# EVB1.net
KiCad netlist of a schematic drawn in Altium Designer
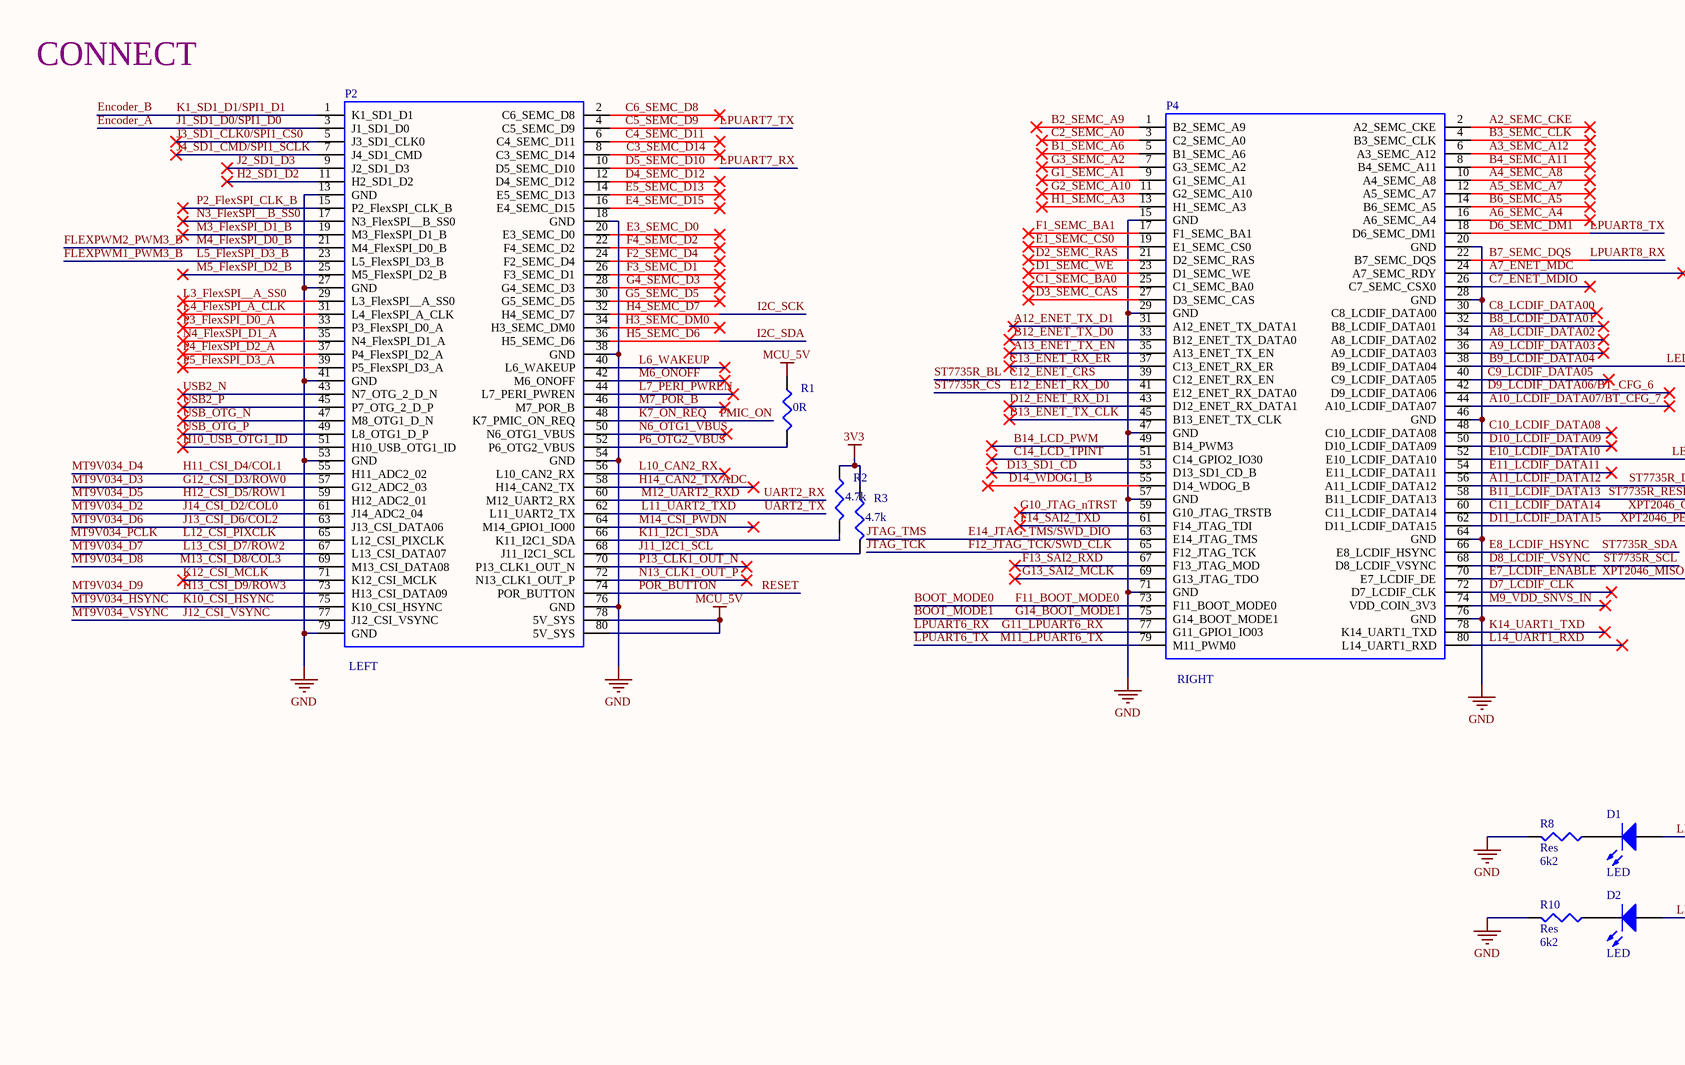
[diagram p0: EVB1.SchDoc, left]
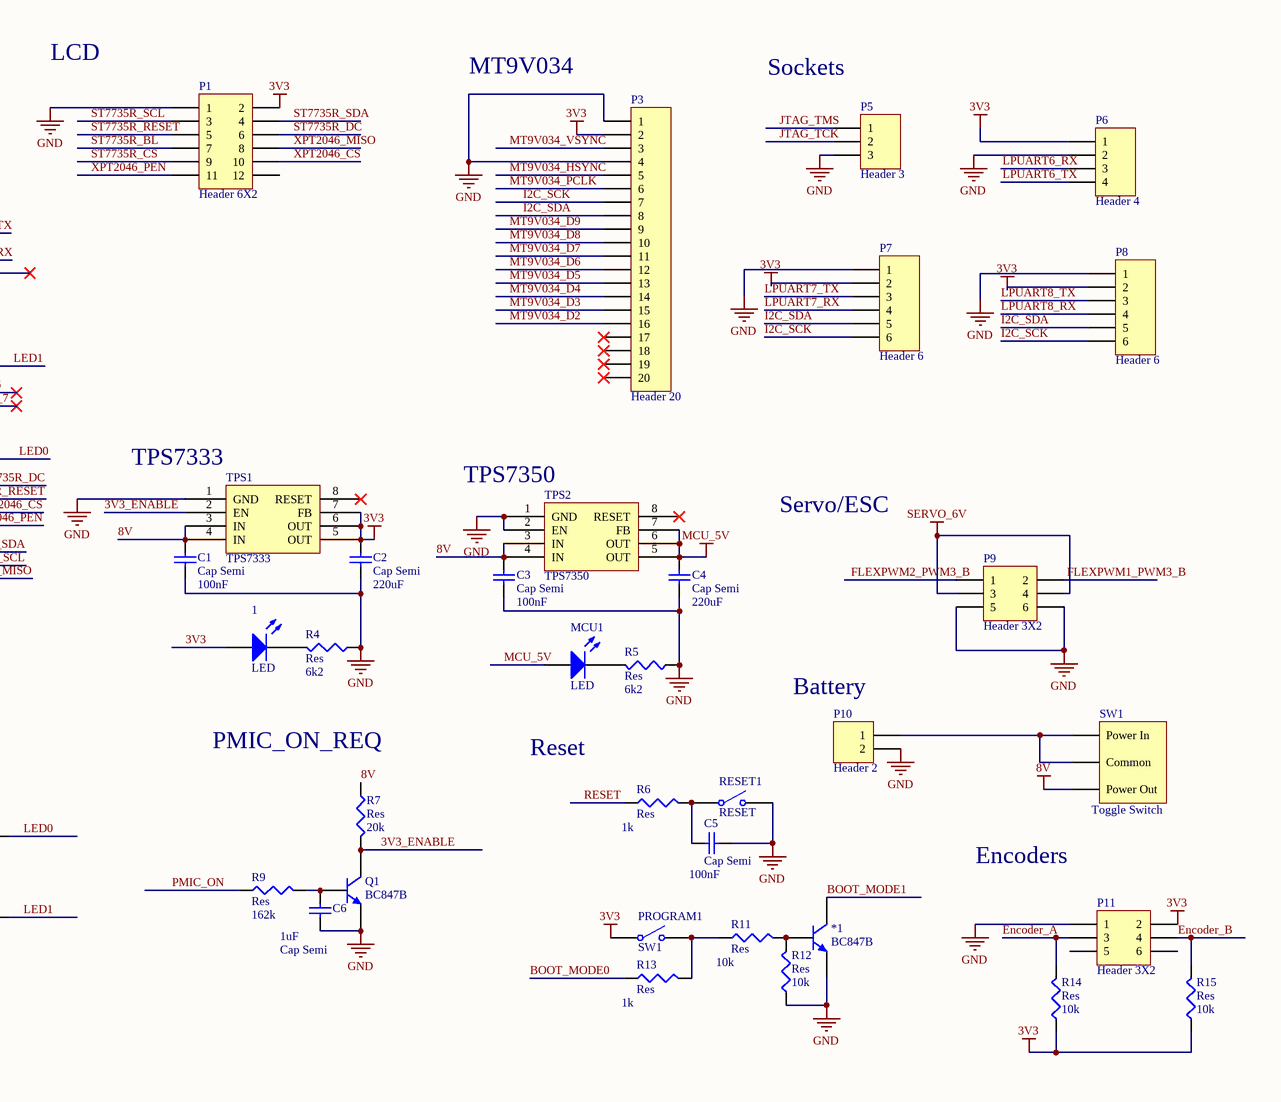
[diagram p1: EVB1.SchDoc, right]

(export (version "E")
  (design (tool "Eeschema 10.0.6"))
  (components
    (comp (ref "*1")
      (value "BC847B")
      (footprint "SOT-23")
      (description "NPN")
      (libsource (lib "SmartCar2018") (part "BC847B"))
    )
    (comp (ref "1")
      (value "LED")
      (footprint "LED 0805")
      (description "Typical GaAs LED")
      (fields (field (name "PUBLISHER") "Altium Limited"))
      (libsource (lib "SmartCar2018") (part "LED"))
    )
    (comp (ref "C1")
      (value "Cap Semi")
      (footprint "CC2012-0805")
      (description "Capacitor (Semiconductor SIM Model)")
      (fields (field (name "ALTIUM_VALUE") "100nF") (field (name "PUBLISHER") "Altium Limited"))
      (libsource (lib "SmartCar2018") (part "Cap Semi"))
    )
    (comp (ref "C2")
      (value "Cap Semi")
      (footprint "CC3216-1206")
      (description "Capacitor (Semiconductor SIM Model)")
      (fields (field (name "ALTIUM_VALUE") "220uF") (field (name "PUBLISHER") "Altium Limited"))
      (libsource (lib "SmartCar2018") (part "Cap Semi"))
    )
    (comp (ref "C3")
      (value "Cap Semi")
      (footprint "CC2012-0805")
      (description "Capacitor (Semiconductor SIM Model)")
      (fields (field (name "ALTIUM_VALUE") "100nF") (field (name "PUBLISHER") "Altium Limited"))
      (libsource (lib "SmartCar2018") (part "Cap Semi"))
    )
    (comp (ref "C4")
      (value "Cap Semi")
      (footprint "CC3216-1206")
      (description "Capacitor (Semiconductor SIM Model)")
      (fields (field (name "ALTIUM_VALUE") "220uF") (field (name "PUBLISHER") "Altium Limited"))
      (libsource (lib "SmartCar2018") (part "Cap Semi"))
    )
    (comp (ref "C5")
      (value "Cap Semi")
      (footprint "CC2012-0805")
      (description "Capacitor (Semiconductor SIM Model)")
      (fields (field (name "ALTIUM_VALUE") "100nF") (field (name "PUBLISHER") "Altium Limited"))
      (libsource (lib "SmartCar2018") (part "Cap Semi"))
    )
    (comp (ref "C6")
      (value "Cap Semi")
      (footprint "CC2012-0805")
      (description "Capacitor (Semiconductor SIM Model)")
      (fields (field (name "ALTIUM_VALUE") "1uF") (field (name "PUBLISHER") "Altium Limited"))
      (libsource (lib "SmartCar2018") (part "Cap Semi"))
    )
    (comp (ref "D1")
      (value "LED")
      (footprint "LED 0805")
      (description "Typical GaAs LED")
      (fields (field (name "PUBLISHER") "Altium Limited"))
      (libsource (lib "SmartCar2018") (part "LED"))
    )
    (comp (ref "D2")
      (value "LED")
      (footprint "LED 0805")
      (description "Typical GaAs LED")
      (fields (field (name "PUBLISHER") "Altium Limited"))
      (libsource (lib "SmartCar2018") (part "LED"))
    )
    (comp (ref "MCU1")
      (value "LED")
      (footprint "LED 0805")
      (description "Typical GaAs LED")
      (fields (field (name "PUBLISHER") "Altium Limited"))
      (libsource (lib "SmartCar2018") (part "LED"))
    )
    (comp (ref "P1")
      (value "Header 6X2")
      (footprint "HDR2X6")
      (description "Header, 6-Pin, Dual row")
      (fields (field (name "PUBLISHER") "Altium Limited"))
      (libsource (lib "SmartCar2018") (part "Header 6X2"))
    )
    (comp (ref "P2")
      (value "LEFT")
      (footprint "CON80:CON80")
      (description "Header, 30-Pin, Dual row")
      (fields (field (name "PUBLISHER") "Altium Limited"))
      (libsource (lib "PCB_RT1052_1") (part "Header40X2_left"))
    )
    (comp (ref "P3")
      (value "Header 20")
      (footprint "FPC0.5_20P")
      (description "Header, 20-Pin")
      (fields (field (name "PUBLISHER") "Altium Limited"))
      (libsource (lib "SmartCar2018") (part "Header 20"))
    )
    (comp (ref "P4")
      (value "RIGHT")
      (footprint "CON80:CON80")
      (description "Header, 30-Pin, Dual row")
      (fields (field (name "PUBLISHER") "Altium Limited"))
      (libsource (lib "PCB_RT1052_1") (part "Header40X2_right"))
    )
    (comp (ref "P5")
      (value "Header 3")
      (footprint "HDR1X3")
      (description "Header, 3-Pin")
      (fields (field (name "PUBLISHER") "Altium Limited"))
      (libsource (lib "SmartCar2018") (part "Header 3"))
    )
    (comp (ref "P6")
      (value "Header 4")
      (footprint "HDR1X4")
      (description "Header, 4-Pin")
      (fields (field (name "PUBLISHER") "Altium Limited"))
      (libsource (lib "SmartCar2018") (part "Header 4"))
    )
    (comp (ref "P7")
      (value "Header 6")
      (footprint "HDR1X6")
      (description "Header, 6-Pin")
      (fields (field (name "PUBLISHER") "Altium Limited"))
      (libsource (lib "SmartCar2018") (part "Header 6"))
    )
    (comp (ref "P8")
      (value "Header 6")
      (footprint "HDR1X6")
      (description "Header, 6-Pin")
      (fields (field (name "PUBLISHER") "Altium Limited"))
      (libsource (lib "SmartCar2018") (part "Header 6"))
    )
    (comp (ref "P9")
      (value "Header 3X2")
      (footprint "HDR2X3")
      (description "Header, 3-Pin, Dual row")
      (fields (field (name "PUBLISHER") "Altium Limited"))
      (libsource (lib "SmartCar2018") (part "Header 3X2"))
    )
    (comp (ref "P10")
      (value "Header 2")
      (footprint "XT30PW-M")
      (description "Header, 2-Pin")
      (fields (field (name "PUBLISHER") "Altium Limited"))
      (libsource (lib "SmartCar2018") (part "Header 2"))
    )
    (comp (ref "P11")
      (value "Header 3X2")
      (footprint "SMMD HEADER 2X3")
      (description "Header, 3-Pin, Dual row")
      (fields (field (name "PUBLISHER") "Altium Limited"))
      (libsource (lib "SmartCar2018") (part "Header 3X2"))
    )
    (comp (ref "PROGRAM1")
      (value "SW1")
      (footprint "PUSHBUTTOM")
      (description "Single-Pole, Single-Throw Switch")
      (fields (field (name "PUBLISHER") "Altium Limited"))
      (libsource (lib "SmartCar2018") (part "SW-SPST"))
    )
    (comp (ref "Q1")
      (value "BC847B")
      (footprint "SOT-23")
      (description "NPN")
      (libsource (lib "SmartCar2018") (part "BC847B"))
    )
    (comp (ref "R1")
      (value "0R")
      (footprint "CR2012-0805")
      (description "Resistor")
      (fields (field (name "PUBLISHER") "Altium Limited"))
      (libsource (lib "SmartCar2018") (part "Res"))
    )
    (comp (ref "R2")
      (value "4.7k")
      (footprint "CR2012-0805")
      (description "Resistor")
      (fields (field (name "PUBLISHER") "Altium Limited"))
      (libsource (lib "SmartCar2018") (part "Res"))
    )
    (comp (ref "R3")
      (value "4.7k")
      (footprint "CR2012-0805")
      (description "Resistor")
      (fields (field (name "PUBLISHER") "Altium Limited"))
      (libsource (lib "SmartCar2018") (part "Res"))
    )
    (comp (ref "R4")
      (value "Res")
      (footprint "CR2012-0805")
      (description "Resistor")
      (fields (field (name "ALTIUM_VALUE") "6k2") (field (name "PUBLISHER") "Altium Limited"))
      (libsource (lib "SmartCar2018") (part "Res"))
    )
    (comp (ref "R5")
      (value "Res")
      (footprint "CR2012-0805")
      (description "Resistor")
      (fields (field (name "ALTIUM_VALUE") "6k2") (field (name "PUBLISHER") "Altium Limited"))
      (libsource (lib "SmartCar2018") (part "Res"))
    )
    (comp (ref "R6")
      (value "Res")
      (footprint "CR2012-0805")
      (description "Resistor")
      (fields (field (name "ALTIUM_VALUE") "1k") (field (name "PUBLISHER") "Altium Limited"))
      (libsource (lib "SmartCar2018") (part "Res"))
    )
    (comp (ref "R7")
      (value "Res")
      (footprint "CR2012-0805")
      (description "Resistor")
      (fields (field (name "ALTIUM_VALUE") "20k") (field (name "PUBLISHER") "Altium Limited"))
      (libsource (lib "SmartCar2018") (part "Res"))
    )
    (comp (ref "R8")
      (value "Res")
      (footprint "CR2012-0805")
      (description "Resistor")
      (fields (field (name "ALTIUM_VALUE") "6k2") (field (name "PUBLISHER") "Altium Limited"))
      (libsource (lib "SmartCar2018") (part "Res"))
    )
    (comp (ref "R9")
      (value "Res")
      (footprint "CR2012-0805")
      (description "Resistor")
      (fields (field (name "ALTIUM_VALUE") "162k") (field (name "PUBLISHER") "Altium Limited"))
      (libsource (lib "SmartCar2018") (part "Res"))
    )
    (comp (ref "R10")
      (value "Res")
      (footprint "CR2012-0805")
      (description "Resistor")
      (fields (field (name "ALTIUM_VALUE") "6k2") (field (name "PUBLISHER") "Altium Limited"))
      (libsource (lib "SmartCar2018") (part "Res"))
    )
    (comp (ref "R11")
      (value "Res")
      (footprint "CR2012-0805")
      (description "Resistor")
      (fields (field (name "ALTIUM_VALUE") "10k") (field (name "PUBLISHER") "Altium Limited"))
      (libsource (lib "SmartCar2018") (part "Res"))
    )
    (comp (ref "R12")
      (value "Res")
      (footprint "CR2012-0805")
      (description "Resistor")
      (fields (field (name "ALTIUM_VALUE") "10k") (field (name "PUBLISHER") "Altium Limited"))
      (libsource (lib "SmartCar2018") (part "Res"))
    )
    (comp (ref "R13")
      (value "Res")
      (footprint "CR2012-0805")
      (description "Resistor")
      (fields (field (name "ALTIUM_VALUE") "1k") (field (name "PUBLISHER") "Altium Limited"))
      (libsource (lib "SmartCar2018") (part "Res"))
    )
    (comp (ref "R14")
      (value "Res")
      (footprint "CR2012-0805")
      (description "Resistor")
      (fields (field (name "ALTIUM_VALUE") "10k") (field (name "PUBLISHER") "Altium Limited"))
      (libsource (lib "SmartCar2018") (part "Res"))
    )
    (comp (ref "R15")
      (value "Res")
      (footprint "CR2012-0805")
      (description "Resistor")
      (fields (field (name "ALTIUM_VALUE") "10k") (field (name "PUBLISHER") "Altium Limited"))
      (libsource (lib "SmartCar2018") (part "Res"))
    )
    (comp (ref "RESET1")
      (value "RESET")
      (footprint "PUSHBUTTOM")
      (description "Single-Pole, Single-Throw Switch")
      (fields (field (name "PUBLISHER") "Altium Limited"))
      (libsource (lib "SmartCar2018") (part "SW-SPST"))
    )
    (comp (ref "SW1")
      (value "Toggle Switch")
      (footprint "ToggleSwitch")
      (description "Power toggle switch")
      (libsource (lib "SmartCar2018") (part "ToggleSwitch"))
    )
    (comp (ref "TPS1")
      (value "TPS7333")
      (footprint "TPS7333")
      (libsource (lib "SmartCar2018") (part "TPS7333"))
    )
    (comp (ref "TPS2")
      (value "TPS7350")
      (footprint "TPS7333")
      (libsource (lib "SmartCar2018") (part "TPS7333"))
    )
  )
  (nets
    (net (code "1") (name "/3V3_ENABLE") (class "Default")
      (node (ref "Q1") (pin "3") (pinfunction "C_3") (pintype "passive"))
      (node (ref "R7") (pin "2") (pinfunction "2_2") (pintype "passive"))
      (node (ref "TPS1") (pin "2") (pinfunction "EN_2") (pintype "passive"))
    )
    (net (code "2") (name "/A2_SEMC_CKE") (class "Default")
      (node (ref "P4") (pin "2") (pinfunction "A2_SEMC_CKE_2") (pintype "passive+no_connect"))
    )
    (net (code "3") (name "/A3_SEMC_A12") (class "Default")
      (node (ref "P4") (pin "6") (pinfunction "A3_SEMC_A12_6") (pintype "passive+no_connect"))
    )
    (net (code "4") (name "/A4_SEMC_A8") (class "Default")
      (node (ref "P4") (pin "10") (pinfunction "A4_SEMC_A8_10") (pintype "passive+no_connect"))
    )
    (net (code "5") (name "/A5_SEMC_A7") (class "Default")
      (node (ref "P4") (pin "12") (pinfunction "A5_SEMC_A7_12") (pintype "passive+no_connect"))
    )
    (net (code "6") (name "/A6_SEMC_A4") (class "Default")
      (node (ref "P4") (pin "16") (pinfunction "A6_SEMC_A4_16") (pintype "passive+no_connect"))
    )
    (net (code "7") (name "/A7_ENET_MDC") (class "Default")
      (node (ref "P4") (pin "24") (pinfunction "A7_SEMC_RDY_24") (pintype "passive+no_connect"))
    )
    (net (code "8") (name "/A8_LCDIF_DATA02") (class "Default")
      (node (ref "P4") (pin "34") (pinfunction "A8_LCDIF_DATA02_34") (pintype "passive+no_connect"))
    )
    (net (code "9") (name "/A9_LCDIF_DATA03") (class "Default")
      (node (ref "P4") (pin "36") (pinfunction "A9_LCDIF_DATA03_36") (pintype "passive+no_connect"))
    )
    (net (code "10") (name "/A10_LCDIF_DATA07{slash}BT_CFG_7") (class "Default")
      (node (ref "P4") (pin "44") (pinfunction "A10_LCDIF_DATA07_44") (pintype "passive+no_connect"))
    )
    (net (code "11") (name "/A11_LCDIF_DATA12") (class "Default")
      (node (ref "P1") (pin "6") (pinfunction "6_6") (pintype "passive"))
      (node (ref "P4") (pin "56") (pinfunction "A11_LCDIF_DATA12_56") (pintype "passive"))
    )
    (net (code "13") (name "/A12_ENET_TX_D1") (class "Default")
      (node (ref "P4") (pin "31") (pinfunction "A12_ENET_TX_DATA1_31") (pintype "passive"))
    )
    (net (code "14") (name "/A13_ENET_TX_EN") (class "Default")
      (node (ref "P4") (pin "35") (pinfunction "A13_ENET_TX_EN_35") (pintype "passive+no_connect"))
    )
    (net (code "15") (name "/B1_SEMC_A6") (class "Default")
      (node (ref "P4") (pin "5") (pinfunction "B1_SEMC_A6_5") (pintype "passive+no_connect"))
    )
    (net (code "16") (name "/B2_SEMC_A9") (class "Default")
      (node (ref "P4") (pin "1") (pinfunction "B2_SEMC_A9_1") (pintype "passive+no_connect"))
    )
    (net (code "17") (name "/B3_SEMC_CLK") (class "Default")
      (node (ref "P4") (pin "4") (pinfunction "B3_SEMC_CLK_4") (pintype "passive+no_connect"))
    )
    (net (code "18") (name "/B4_SEMC_A11") (class "Default")
      (node (ref "P4") (pin "8") (pinfunction "B4_SEMC_A11_8") (pintype "passive+no_connect"))
    )
    (net (code "19") (name "/B6_SEMC_A5") (class "Default")
      (node (ref "P4") (pin "14") (pinfunction "B6_SEMC_A5_14") (pintype "passive+no_connect"))
    )
    (net (code "20") (name "/B7_SEMC_DQS") (class "Default")
      (node (ref "P4") (pin "22") (pinfunction "B7_SEMC_DQS_22") (pintype "passive"))
      (node (ref "P8") (pin "4") (pinfunction "4_4") (pintype "passive"))
    )
    (net (code "21") (name "/B8_LCDIF_DATA01") (class "Default")
      (node (ref "P4") (pin "32") (pinfunction "B8_LCDIF_DATA01_32") (pintype "passive+no_connect"))
    )
    (net (code "22") (name "/B9_LCDIF_DATA04") (class "Default")
      (node (ref "D2") (pin "1") (pinfunction "A_1") (pintype "passive"))
      (node (ref "P4") (pin "38") (pinfunction "B9_LCDIF_DATA04_38") (pintype "passive"))
    )
    (net (code "23") (name "/B11_LCDIF_DATA13") (class "Default")
      (node (ref "P1") (pin "5") (pinfunction "5_5") (pintype "passive"))
      (node (ref "P4") (pin "58") (pinfunction "B11_LCDIF_DATA13_58") (pintype "passive"))
    )
    (net (code "24") (name "/B12_ENET_TX_D0") (class "Default")
      (node (ref "P4") (pin "33") (pinfunction "B12_ENET_TX_DATA0_33") (pintype "passive+no_connect"))
    )
    (net (code "25") (name "/B13_ENET_TX_CLK") (class "Default")
      (node (ref "P4") (pin "45") (pinfunction "B13_ENET_TX_CLK_45") (pintype "passive+no_connect"))
    )
    (net (code "26") (name "/B14_LCD_PWM") (class "Default")
      (node (ref "P4") (pin "49") (pinfunction "B14_PWM3_49") (pintype "passive+no_connect"))
    )
    (net (code "27") (name "/BOOT_MODE0") (class "Default")
      (node (ref "P4") (pin "73") (pinfunction "F11_BOOT_MODE0_73") (pintype "passive"))
      (node (ref "R13") (pin "1") (pinfunction "1_1") (pintype "passive"))
    )
    (net (code "28") (name "/BOOT_MODE1") (class "Default")
      (node (ref "*1") (pin "3") (pinfunction "C_3") (pintype "passive"))
      (node (ref "P4") (pin "75") (pinfunction "G14_BOOT_MODE1_75") (pintype "passive"))
    )
    (net (code "29") (name "/C1_SEMC_BA0") (class "Default")
      (node (ref "P4") (pin "25") (pinfunction "C1_SEMC_BA0_25") (pintype "passive+no_connect"))
    )
    (net (code "30") (name "/C2_SEMC_A0") (class "Default")
      (node (ref "P4") (pin "3") (pinfunction "C2_SEMC_A0_3") (pintype "passive+no_connect"))
    )
    (net (code "31") (name "/C3_SEMC_D14") (class "Default")
      (node (ref "P2") (pin "8") (pinfunction "C3_SEMC_D14_8") (pintype "passive+no_connect"))
    )
    (net (code "32") (name "/C4_SEMC_D11") (class "Default")
      (node (ref "P2") (pin "6") (pinfunction "C4_SEMC_D11_6") (pintype "passive+no_connect"))
    )
    (net (code "33") (name "/C5_SEMC_D9") (class "Default")
      (node (ref "P2") (pin "4") (pinfunction "C5_SEMC_D9_4") (pintype "passive"))
      (node (ref "P7") (pin "3") (pinfunction "3_3") (pintype "passive"))
    )
    (net (code "34") (name "/C6_SEMC_D8") (class "Default")
      (node (ref "P2") (pin "2") (pinfunction "C6_SEMC_D8_2") (pintype "passive+no_connect"))
    )
    (net (code "35") (name "/C7_ENET_MDIO") (class "Default")
      (node (ref "P4") (pin "26") (pinfunction "C7_SEMC_CSX0_26") (pintype "passive+no_connect"))
    )
    (net (code "36") (name "/C8_LCDIF_DATA00") (class "Default")
      (node (ref "P4") (pin "30") (pinfunction "C8_LCDIF_DATA00_30") (pintype "passive+no_connect"))
    )
    (net (code "37") (name "/C9_LCDIF_DATA05") (class "Default")
      (node (ref "P4") (pin "40") (pinfunction "C9_LCDIF_DATA05_40") (pintype "passive+no_connect"))
    )
    (net (code "38") (name "/C10_LCDIF_DATA08") (class "Default")
      (node (ref "P4") (pin "48") (pinfunction "C10_LCDIF_DATA08_48") (pintype "passive+no_connect"))
    )
    (net (code "39") (name "/C11_LCDIF_DATA14") (class "Default")
      (node (ref "P1") (pin "10") (pinfunction "10_10") (pintype "passive"))
      (node (ref "P4") (pin "60") (pinfunction "C11_LCDIF_DATA14_60") (pintype "passive"))
    )
    (net (code "40") (name "/C12_ENET_CRS") (class "Default")
      (node (ref "P1") (pin "7") (pinfunction "7_7") (pintype "passive"))
      (node (ref "P4") (pin "39") (pinfunction "C12_ENET_RX_EN_39") (pintype "passive"))
    )
    (net (code "41") (name "/C13_ENET_RX_ER") (class "Default")
      (node (ref "P4") (pin "37") (pinfunction "C13_ENET_RX_ER_37") (pintype "passive+no_connect"))
    )
    (net (code "42") (name "/C14_LCD_TPINT") (class "Default")
      (node (ref "P4") (pin "51") (pinfunction "C14_GPIO2_IO30_51") (pintype "passive+no_connect"))
    )
    (net (code "43") (name "/D1_SEMC_WE") (class "Default")
      (node (ref "P4") (pin "23") (pinfunction "D1_SEMC_WE_23") (pintype "passive+no_connect"))
    )
    (net (code "44") (name "/D2_SEMC_RAS") (class "Default")
      (node (ref "P4") (pin "21") (pinfunction "D2_SEMC_RAS_21") (pintype "passive+no_connect"))
    )
    (net (code "45") (name "/D3_SEMC_CAS") (class "Default")
      (node (ref "P4") (pin "27") (pinfunction "D3_SEMC_CAS_27") (pintype "passive+no_connect"))
    )
    (net (code "46") (name "/D4_SEMC_D12") (class "Default")
      (node (ref "P2") (pin "12") (pinfunction "D4_SEMC_D12_12") (pintype "passive+no_connect"))
    )
    (net (code "47") (name "/D5_SEMC_D10") (class "Default")
      (node (ref "P2") (pin "10") (pinfunction "D5_SEMC_D10_10") (pintype "passive"))
      (node (ref "P7") (pin "4") (pinfunction "4_4") (pintype "passive"))
    )
    (net (code "48") (name "/D6_SEMC_DM1") (class "Default")
      (node (ref "P4") (pin "18") (pinfunction "D6_SEMC_DM1_18") (pintype "passive"))
      (node (ref "P8") (pin "3") (pinfunction "3_3") (pintype "passive"))
    )
    (net (code "49") (name "/D7_LCDIF_CLK") (class "Default")
      (node (ref "P4") (pin "72") (pinfunction "D7_LCDIF_CLK_72") (pintype "passive+no_connect"))
    )
    (net (code "50") (name "/D8_LCDIF_VSYNC") (class "Default")
      (node (ref "P1") (pin "3") (pinfunction "3_3") (pintype "passive"))
      (node (ref "P4") (pin "68") (pinfunction "D8_LCDIF_VSYNC_68") (pintype "passive"))
    )
    (net (code "51") (name "/D9_LCDIF_DATA06{slash}BT_CFG_6") (class "Default")
      (node (ref "P4") (pin "42") (pinfunction "D9_LCDIF_DATA06_42") (pintype "passive+no_connect"))
    )
    (net (code "52") (name "/D10_LCDIF_DATA09") (class "Default")
      (node (ref "P4") (pin "50") (pinfunction "D10_LCDIF_DATA09_50") (pintype "passive+no_connect"))
    )
    (net (code "53") (name "/D11_LCDIF_DATA15") (class "Default")
      (node (ref "P1") (pin "11") (pinfunction "11_11") (pintype "passive"))
      (node (ref "P4") (pin "62") (pinfunction "D11_LCDIF_DATA15_62") (pintype "passive"))
    )
    (net (code "54") (name "/D12_ENET_RX_D1") (class "Default")
      (node (ref "P4") (pin "43") (pinfunction "D12_ENET_RX_DATA1_43") (pintype "passive+no_connect"))
    )
    (net (code "55") (name "/D13_SD1_CD") (class "Default")
      (node (ref "P4") (pin "53") (pinfunction "D13_SD1_CD_B_53") (pintype "passive+no_connect"))
    )
    (net (code "56") (name "/D14_WDOG1_B") (class "Default")
      (node (ref "P4") (pin "55") (pinfunction "D14_WDOG_B_55") (pintype "passive+no_connect"))
    )
    (net (code "57") (name "/E1_SEMC_CS0") (class "Default")
      (node (ref "P4") (pin "19") (pinfunction "E1_SEMC_CS0_19") (pintype "passive+no_connect"))
    )
    (net (code "58") (name "/E3_SEMC_D0") (class "Default")
      (node (ref "P2") (pin "20") (pinfunction "E3_SEMC_D0_20") (pintype "passive+no_connect"))
    )
    (net (code "59") (name "/E4_SEMC_D15") (class "Default")
      (node (ref "P2") (pin "16") (pinfunction "E4_SEMC_D15_16") (pintype "passive+no_connect"))
    )
    (net (code "60") (name "/E5_SEMC_D13") (class "Default")
      (node (ref "P2") (pin "14") (pinfunction "E5_SEMC_D13_14") (pintype "passive+no_connect"))
    )
    (net (code "61") (name "/E7_LCDIF_ENABLE") (class "Default")
      (node (ref "P1") (pin "8") (pinfunction "8_8") (pintype "passive"))
      (node (ref "P4") (pin "70") (pinfunction "E7_LCDIF_DE_70") (pintype "passive"))
    )
    (net (code "62") (name "/E8_LCDIF_HSYNC") (class "Default")
      (node (ref "P1") (pin "4") (pinfunction "4_4") (pintype "passive"))
      (node (ref "P4") (pin "66") (pinfunction "E8_LCDIF_HSYNC_66") (pintype "passive"))
    )
    (net (code "63") (name "/E10_LCDIF_DATA10") (class "Default")
      (node (ref "D1") (pin "1") (pinfunction "A_1") (pintype "passive"))
      (node (ref "P4") (pin "52") (pinfunction "E10_LCDIF_DATA10_52") (pintype "passive"))
    )
    (net (code "64") (name "/E11_LCDIF_DATA11") (class "Default")
      (node (ref "P4") (pin "54") (pinfunction "E11_LCDIF_DATA11_54") (pintype "passive+no_connect"))
    )
    (net (code "65") (name "/E12_ENET_RX_D0") (class "Default")
      (node (ref "P1") (pin "9") (pinfunction "9_9") (pintype "passive"))
      (node (ref "P4") (pin "41") (pinfunction "E12_ENET_RX_DATA0_41") (pintype "passive"))
    )
    (net (code "66") (name "/E14_JTAG_TMS{slash}SWD_DIO") (class "Default")
      (node (ref "P4") (pin "63") (pinfunction "E14_JTAG_TMS_63") (pintype "passive"))
      (node (ref "P5") (pin "1") (pinfunction "1_1") (pintype "passive"))
    )
    (net (code "67") (name "/Encoder_A") (class "Default")
      (node (ref "P11") (pin "3") (pinfunction "3_3") (pintype "passive"))
      (node (ref "P2") (pin "3") (pinfunction "J1_SD1_D0_3") (pintype "passive"))
      (node (ref "R14") (pin "2") (pinfunction "2_2") (pintype "passive"))
    )
    (net (code "68") (name "/Encoder_B") (class "Default")
      (node (ref "P11") (pin "4") (pinfunction "4_4") (pintype "passive"))
      (node (ref "P2") (pin "1") (pinfunction "K1_SD1_D1_1") (pintype "passive"))
      (node (ref "R15") (pin "2") (pinfunction "2_2") (pintype "passive"))
    )
    (net (code "69") (name "/F1_SEMC_BA1") (class "Default")
      (node (ref "P4") (pin "17") (pinfunction "F1_SEMC_BA1_17") (pintype "passive+no_connect"))
    )
    (net (code "70") (name "/F2_SEMC_D4") (class "Default")
      (node (ref "P2") (pin "24") (pinfunction "F2_SEMC_D4_24") (pintype "passive+no_connect"))
    )
    (net (code "71") (name "/F3_SEMC_D1") (class "Default")
      (node (ref "P2") (pin "26") (pinfunction "F3_SEMC_D1_26") (pintype "passive+no_connect"))
    )
    (net (code "72") (name "/F4_SEMC_D2") (class "Default")
      (node (ref "P2") (pin "22") (pinfunction "F4_SEMC_D2_22") (pintype "passive+no_connect"))
    )
    (net (code "73") (name "/F12_JTAG_TCK{slash}SWD_CLK") (class "Default")
      (node (ref "P4") (pin "65") (pinfunction "F12_JTAG_TCK_65") (pintype "passive"))
      (node (ref "P5") (pin "2") (pinfunction "2_2") (pintype "passive"))
    )
    (net (code "74") (name "/F13_SAI2_RXD") (class "Default")
      (node (ref "P4") (pin "67") (pinfunction "F13_JTAG_MOD_67") (pintype "passive+no_connect"))
    )
    (net (code "75") (name "/F14_SAI2_TXD") (class "Default")
      (node (ref "P4") (pin "61") (pinfunction "F14_JTAG_TDI_61") (pintype "passive+no_connect"))
    )
    (net (code "76") (name "/FLEXPWM1_PWM3_B") (class "Default")
      (node (ref "P2") (pin "23") (pinfunction "L5_FlexSPI_D3_B_23") (pintype "passive"))
      (node (ref "P9") (pin "2") (pinfunction "2_2") (pintype "passive"))
    )
    (net (code "77") (name "/FLEXPWM2_PWM3_B") (class "Default")
      (node (ref "P2") (pin "21") (pinfunction "M4_FlexSPI_D0_B_21") (pintype "passive"))
      (node (ref "P9") (pin "1") (pinfunction "1_1") (pintype "passive"))
    )
    (net (code "78") (name "/G1_SEMC_A1") (class "Default")
      (node (ref "P4") (pin "9") (pinfunction "G1_SEMC_A1_9") (pintype "passive+no_connect"))
    )
    (net (code "79") (name "/G2_SEMC_A10") (class "Default")
      (node (ref "P4") (pin "11") (pinfunction "G2_SEMC_A10_11") (pintype "passive+no_connect"))
    )
    (net (code "80") (name "/G3_SEMC_A2") (class "Default")
      (node (ref "P4") (pin "7") (pinfunction "G3_SEMC_A2_7") (pintype "passive+no_connect"))
    )
    (net (code "81") (name "/G4_SEMC_D3") (class "Default")
      (node (ref "P2") (pin "28") (pinfunction "G4_SEMC_D3_28") (pintype "passive+no_connect"))
    )
    (net (code "82") (name "/G5_SEMC_D5") (class "Default")
      (node (ref "P2") (pin "30") (pinfunction "G5_SEMC_D5_30") (pintype "passive+no_connect"))
    )
    (net (code "83") (name "/G10_JTAG_nTRST") (class "Default")
      (node (ref "P4") (pin "59") (pinfunction "G10_JTAG_TRSTB_59") (pintype "passive+no_connect"))
    )
    (net (code "84") (name "/G11_LPUART6_RX") (class "Default")
      (node (ref "P4") (pin "77") (pinfunction "G11_GPIO1_IO03_77") (pintype "passive"))
      (node (ref "P6") (pin "3") (pinfunction "3_3") (pintype "passive"))
    )
    (net (code "85") (name "/G12_CSI_D3{slash}ROW0") (class "Default")
      (node (ref "P2") (pin "57") (pinfunction "G12_ADC2_03_57") (pintype "passive"))
      (node (ref "P3") (pin "15") (pinfunction "15_15") (pintype "passive"))
    )
    (net (code "86") (name "/G13_SAI2_MCLK") (class "Default")
      (node (ref "P4") (pin "69") (pinfunction "G13_JTAG_TDO_69") (pintype "passive+no_connect"))
    )
    (net (code "87") (name "/H1_SEMC_A3") (class "Default")
      (node (ref "P4") (pin "13") (pinfunction "H1_SEMC_A3_13") (pintype "passive+no_connect"))
    )
    (net (code "88") (name "/H2_SD1_D2") (class "Default")
      (node (ref "P2") (pin "11") (pinfunction "H2_SD1_D2_11") (pintype "passive+no_connect"))
    )
    (net (code "89") (name "/H3_SEMC_DM0") (class "Default")
      (node (ref "P2") (pin "34") (pinfunction "H3_SEMC_DM0_34") (pintype "passive+no_connect"))
    )
    (net (code "90") (name "/H4_SEMC_D7") (class "Default")
      (node (ref "P2") (pin "32") (pinfunction "H4_SEMC_D7_32") (pintype "passive"))
      (node (ref "P3") (pin "7") (pinfunction "7_7") (pintype "passive"))
      (node (ref "P7") (pin "6") (pinfunction "6_6") (pintype "passive"))
      (node (ref "P8") (pin "6") (pinfunction "6_6") (pintype "passive"))
    )
    (net (code "91") (name "/H5_SEMC_D6") (class "Default")
      (node (ref "P2") (pin "36") (pinfunction "H5_SEMC_D6_36") (pintype "passive"))
      (node (ref "P3") (pin "8") (pinfunction "8_8") (pintype "passive"))
      (node (ref "P7") (pin "5") (pinfunction "5_5") (pintype "passive"))
      (node (ref "P8") (pin "5") (pinfunction "5_5") (pintype "passive"))
    )
    (net (code "92") (name "/H10_USB_OTG1_ID") (class "Default")
      (node (ref "P2") (pin "51") (pinfunction "H10_USB_OTG1_ID_51") (pintype "passive+no_connect"))
    )
    (net (code "93") (name "/H11_CSI_D4{slash}COL1") (class "Default")
      (node (ref "P2") (pin "55") (pinfunction "H11_ADC2_02_55") (pintype "passive"))
      (node (ref "P3") (pin "14") (pinfunction "14_14") (pintype "passive"))
    )
    (net (code "94") (name "/H12_CSI_D5{slash}ROW1") (class "Default")
      (node (ref "P2") (pin "59") (pinfunction "H12_ADC2_01_59") (pintype "passive"))
      (node (ref "P3") (pin "13") (pinfunction "13_13") (pintype "passive"))
    )
    (net (code "95") (name "/H13_CSI_D9{slash}ROW3") (class "Default")
      (node (ref "P2") (pin "73") (pinfunction "H13_CSI_DATA09_73") (pintype "passive"))
      (node (ref "P3") (pin "9") (pinfunction "9_9") (pintype "passive"))
    )
    (net (code "96") (name "/H14_CAN2_TX{slash}ADC") (class "Default")
      (node (ref "P2") (pin "58") (pinfunction "H14_CAN2_TX_58") (pintype "passive+no_connect"))
    )
    (net (code "97") (name "/J2_SD1_D3") (class "Default")
      (node (ref "P2") (pin "9") (pinfunction "J2_SD1_D3_9") (pintype "passive+no_connect"))
    )
    (net (code "98") (name "/J3_SD1_CLK0{slash}SPI1_CS0") (class "Default")
      (node (ref "P2") (pin "5") (pinfunction "J3_SD1_CLK0_5") (pintype "passive+no_connect"))
    )
    (net (code "99") (name "/J4_SD1_CMD{slash}SPI1_SCLK") (class "Default")
      (node (ref "P2") (pin "7") (pinfunction "J4_SD1_CMD_7") (pintype "passive+no_connect"))
    )
    (net (code "100") (name "/J11_I2C1_SCL") (class "Default")
      (node (ref "P2") (pin "68") (pinfunction "J11_I2C1_SCL_68") (pintype "passive"))
      (node (ref "R3") (pin "2") (pinfunction "2_2") (pintype "passive"))
    )
    (net (code "101") (name "/J12_CSI_VSYNC") (class "Default")
      (node (ref "P2") (pin "77") (pinfunction "J12_CSI_VSYNC_77") (pintype "passive"))
      (node (ref "P3") (pin "3") (pinfunction "3_3") (pintype "passive"))
    )
    (net (code "102") (name "/J13_CSI_D6{slash}COL2") (class "Default")
      (node (ref "P2") (pin "63") (pinfunction "J13_CSI_DATA06_63") (pintype "passive"))
      (node (ref "P3") (pin "12") (pinfunction "12_12") (pintype "passive"))
    )
    (net (code "103") (name "/J14_CSI_D2{slash}COL0") (class "Default")
      (node (ref "P2") (pin "61") (pinfunction "J14_ADC2_04_61") (pintype "passive"))
      (node (ref "P3") (pin "16") (pinfunction "16_16") (pintype "passive"))
    )
    (net (code "104") (name "/K7_ON_REQ") (class "Default")
      (node (ref "P2") (pin "48") (pinfunction "K7_PMIC_ON_REQ_48") (pintype "passive"))
      (node (ref "R9") (pin "1") (pinfunction "1_1") (pintype "passive"))
    )
    (net (code "105") (name "/K10_CSI_HSYNC") (class "Default")
      (node (ref "P2") (pin "75") (pinfunction "K10_CSI_HSYNC_75") (pintype "passive"))
      (node (ref "P3") (pin "5") (pinfunction "5_5") (pintype "passive"))
    )
    (net (code "106") (name "/K11_I2C1_SDA") (class "Default")
      (node (ref "P2") (pin "66") (pinfunction "K11_I2C1_SDA_66") (pintype "passive"))
      (node (ref "R2") (pin "2") (pinfunction "2_2") (pintype "passive"))
    )
    (net (code "107") (name "/K12_CSI_MCLK") (class "Default")
      (node (ref "P2") (pin "71") (pinfunction "K12_CSI_MCLK_71") (pintype "passive+no_connect"))
    )
    (net (code "108") (name "/K14_UART1_TXD") (class "Default")
      (node (ref "P4") (pin "78") (pinfunction "K14_UART1_TXD_78") (pintype "passive+no_connect"))
    )
    (net (code "109") (name "/L3_FlexSPI__A_SS0") (class "Default")
      (node (ref "P2") (pin "29") (pinfunction "L3_FlexSPI__A_SS0_29") (pintype "passive+no_connect"))
    )
    (net (code "110") (name "/L4_FlexSPI_A_CLK") (class "Default")
      (node (ref "P2") (pin "31") (pinfunction "L4_FlexSPI_A_CLK_31") (pintype "passive+no_connect"))
    )
    (net (code "111") (name "/L6_WAKEUP") (class "Default")
      (node (ref "P2") (pin "40") (pinfunction "L6_WAKEUP_40") (pintype "passive+no_connect"))
    )
    (net (code "112") (name "/L7_PERI_PWREN") (class "Default")
      (node (ref "P2") (pin "44") (pinfunction "L7_PERI_PWREN_44") (pintype "passive+no_connect"))
    )
    (net (code "113") (name "/L10_CAN2_RX") (class "Default")
      (node (ref "P2") (pin "56") (pinfunction "L10_CAN2_RX_56") (pintype "passive+no_connect"))
    )
    (net (code "114") (name "/L11_UART2_TXD") (class "Default")
      (node (ref "P2") (pin "62") (pinfunction "L11_UART2_TX_62") (pintype "passive"))
    )
    (net (code "115") (name "/L12_CSI_PIXCLK") (class "Default")
      (node (ref "P2") (pin "65") (pinfunction "L12_CSI_PIXCLK_65") (pintype "passive"))
      (node (ref "P3") (pin "6") (pinfunction "6_6") (pintype "passive"))
    )
    (net (code "116") (name "/L13_CSI_D7{slash}ROW2") (class "Default")
      (node (ref "P2") (pin "67") (pinfunction "L13_CSI_DATA07_67") (pintype "passive"))
      (node (ref "P3") (pin "11") (pinfunction "11_11") (pintype "passive"))
    )
    (net (code "117") (name "/L14_UART1_RXD") (class "Default")
      (node (ref "P4") (pin "80") (pinfunction "L14_UART1_RXD_80") (pintype "passive+no_connect"))
    )
    (net (code "118") (name "/LPUART6_TX") (class "Default")
      (node (ref "P4") (pin "79") (pinfunction "M11_PWM0_79") (pintype "passive"))
      (node (ref "P6") (pin "4") (pinfunction "4_4") (pintype "passive"))
    )
    (net (code "119") (name "/M3_FlexSPI_D1_B") (class "Default")
      (node (ref "P2") (pin "19") (pinfunction "M3_FlexSPI_D1_B_19") (pintype "passive+no_connect"))
    )
    (net (code "120") (name "/M5_FlexSPI_D2_B") (class "Default")
      (node (ref "P2") (pin "25") (pinfunction "M5_FlexSPI_D2_B_25") (pintype "passive+no_connect"))
    )
    (net (code "121") (name "/M6_ONOFF") (class "Default")
      (node (ref "P2") (pin "42") (pinfunction "M6_ONOFF_42") (pintype "passive+no_connect"))
    )
    (net (code "122") (name "/M7_POR_B") (class "Default")
      (node (ref "P2") (pin "46") (pinfunction "M7_POR_B_46") (pintype "passive+no_connect"))
    )
    (net (code "123") (name "/M9_VDD_SNVS_IN") (class "Default")
      (node (ref "P4") (pin "74") (pinfunction "VDD_COIN_3V3_74") (pintype "passive+no_connect"))
    )
    (net (code "124") (name "/M12_UART2_RXD") (class "Default")
      (node (ref "P2") (pin "60") (pinfunction "M12_UART2_RX_60") (pintype "passive"))
    )
    (net (code "125") (name "/M13_CSI_D8{slash}COL3") (class "Default")
      (node (ref "P2") (pin "69") (pinfunction "M13_CSI_DATA08_69") (pintype "passive"))
      (node (ref "P3") (pin "10") (pinfunction "10_10") (pintype "passive"))
    )
    (net (code "126") (name "/M14_CSI_PWDN") (class "Default")
      (node (ref "P2") (pin "64") (pinfunction "M14_GPIO1_IO00_64") (pintype "passive+no_connect"))
    )
    (net (code "127") (name "/N3_FlexSPI__B_SS0") (class "Default")
      (node (ref "P2") (pin "17") (pinfunction "N3_FlexSPI__B_SS0_17") (pintype "passive+no_connect"))
    )
    (net (code "128") (name "/N4_FlexSPI_D1_A") (class "Default")
      (node (ref "P2") (pin "35") (pinfunction "N4_FlexSPI_D1_A_35") (pintype "passive+no_connect"))
    )
    (net (code "129") (name "/N6_OTG1_VBUS") (class "Default")
      (node (ref "P2") (pin "50") (pinfunction "N6_OTG1_VBUS_50") (pintype "passive+no_connect"))
    )
    (net (code "130") (name "/N13_CLK1_OUT_P") (class "Default")
      (node (ref "P2") (pin "72") (pinfunction "N13_CLK1_OUT_P_72") (pintype "passive+no_connect"))
    )
    (net (code "131") (name "/P2_FlexSPI_CLK_B") (class "Default")
      (node (ref "P2") (pin "15") (pinfunction "P2_FlexSPI_CLK_B_15") (pintype "passive+no_connect"))
    )
    (net (code "132") (name "/P3_FlexSPI_D0_A") (class "Default")
      (node (ref "P2") (pin "33") (pinfunction "P3_FlexSPI_D0_A_33") (pintype "passive+no_connect"))
    )
    (net (code "133") (name "/P4_FlexSPI_D2_A") (class "Default")
      (node (ref "P2") (pin "37") (pinfunction "P4_FlexSPI_D2_A_37") (pintype "passive+no_connect"))
    )
    (net (code "134") (name "/P5_FlexSPI_D3_A") (class "Default")
      (node (ref "P2") (pin "39") (pinfunction "P5_FlexSPI_D3_A_39") (pintype "passive+no_connect"))
    )
    (net (code "135") (name "/P6_OTG2_VBUS") (class "Default")
      (node (ref "P2") (pin "52") (pinfunction "P6_OTG2_VBUS_52") (pintype "passive"))
      (node (ref "R1") (pin "2") (pinfunction "2_2") (pintype "passive"))
    )
    (net (code "136") (name "/P13_CLK1_OUT_N") (class "Default")
      (node (ref "P2") (pin "70") (pinfunction "P13_CLK1_OUT_N_70") (pintype "passive+no_connect"))
    )
    (net (code "137") (name "/POR_BUTTON") (class "Default")
      (node (ref "P2") (pin "74") (pinfunction "POR_BUTTON_74") (pintype "passive"))
      (node (ref "R6") (pin "1") (pinfunction "1_1") (pintype "passive"))
    )
    (net (code "138") (name "/USB2_N") (class "Default")
      (node (ref "P2") (pin "43") (pinfunction "N7_OTG_2_D_N_43") (pintype "passive+no_connect"))
    )
    (net (code "139") (name "/USB2_P") (class "Default")
      (node (ref "P2") (pin "45") (pinfunction "P7_OTG_2_D_P_45") (pintype "passive+no_connect"))
    )
    (net (code "140") (name "/USB_OTG_N") (class "Default")
      (node (ref "P2") (pin "47") (pinfunction "M8_OTG1_D_N_47") (pintype "passive+no_connect"))
    )
    (net (code "141") (name "/USB_OTG_P") (class "Default")
      (node (ref "P2") (pin "49") (pinfunction "L8_OTG1_D_P_49") (pintype "passive+no_connect"))
    )
    (net (code "142") (name "3V3") (class "Default")
      (node (ref "1") (pin "1") (pinfunction "A_1") (pintype "passive"))
      (node (ref "C2") (pin "2") (pinfunction "2_2") (pintype "passive"))
      (node (ref "P1") (pin "2") (pinfunction "2_2") (pintype "passive"))
      (node (ref "P11") (pin "2") (pinfunction "2_2") (pintype "passive"))
      (node (ref "P3") (pin "2") (pinfunction "2_2") (pintype "passive"))
      (node (ref "P6") (pin "1") (pinfunction "1_1") (pintype "passive"))
      (node (ref "P7") (pin "2") (pinfunction "2_2") (pintype "passive"))
      (node (ref "P8") (pin "2") (pinfunction "2_2") (pintype "passive"))
      (node (ref "PROGRAM1") (pin "1") (pinfunction "COMMON_1") (pintype "passive"))
      (node (ref "R14") (pin "1") (pinfunction "1_1") (pintype "passive"))
      (node (ref "R15") (pin "1") (pinfunction "1_1") (pintype "passive"))
      (node (ref "R2") (pin "1") (pinfunction "1_1") (pintype "passive"))
      (node (ref "R3") (pin "1") (pinfunction "1_1") (pintype "passive"))
      (node (ref "TPS1") (pin "5") (pinfunction "OUT_5") (pintype "passive"))
      (node (ref "TPS1") (pin "6") (pinfunction "OUT_6") (pintype "passive"))
      (node (ref "TPS1") (pin "7") (pinfunction "FB_7") (pintype "passive"))
    )
    (net (code "143") (name "8V") (class "Default")
      (node (ref "C1") (pin "2") (pinfunction "2_2") (pintype "passive"))
      (node (ref "C3") (pin "2") (pinfunction "2_2") (pintype "passive"))
      (node (ref "R7") (pin "1") (pinfunction "1_1") (pintype "passive"))
      (node (ref "SW1") (pin "1") (pinfunction "Power_Out_1") (pintype "passive"))
      (node (ref "TPS1") (pin "3") (pinfunction "IN_3") (pintype "passive"))
      (node (ref "TPS1") (pin "4") (pinfunction "IN_4") (pintype "passive"))
      (node (ref "TPS2") (pin "3") (pinfunction "IN_3") (pintype "passive"))
      (node (ref "TPS2") (pin "4") (pinfunction "IN_4") (pintype "passive"))
    )
    (net (code "144") (name "GND") (class "Default")
      (node (ref "*1") (pin "2") (pinfunction "E_2") (pintype "passive"))
      (node (ref "C1") (pin "1") (pinfunction "1_1") (pintype "passive"))
      (node (ref "C2") (pin "1") (pinfunction "1_1") (pintype "passive"))
      (node (ref "C3") (pin "1") (pinfunction "1_1") (pintype "passive"))
      (node (ref "C4") (pin "1") (pinfunction "1_1") (pintype "passive"))
      (node (ref "C5") (pin "2") (pinfunction "2_2") (pintype "passive"))
      (node (ref "C6") (pin "1") (pinfunction "1_1") (pintype "passive"))
      (node (ref "P1") (pin "1") (pinfunction "1_1") (pintype "passive"))
      (node (ref "P10") (pin "2") (pinfunction "2_2") (pintype "passive"))
      (node (ref "P11") (pin "1") (pinfunction "1_1") (pintype "passive"))
      (node (ref "P2") (pin "13") (pinfunction "GND_13") (pintype "passive"))
      (node (ref "P2") (pin "18") (pinfunction "GND_18") (pintype "passive"))
      (node (ref "P2") (pin "27") (pinfunction "GND_27") (pintype "passive"))
      (node (ref "P2") (pin "38") (pinfunction "GND_38") (pintype "passive"))
      (node (ref "P2") (pin "41") (pinfunction "GND_41") (pintype "passive"))
      (node (ref "P2") (pin "53") (pinfunction "GND_53") (pintype "passive"))
      (node (ref "P2") (pin "54") (pinfunction "GND_54") (pintype "passive"))
      (node (ref "P2") (pin "76") (pinfunction "GND_76") (pintype "passive"))
      (node (ref "P2") (pin "79") (pinfunction "GND_79") (pintype "passive"))
      (node (ref "P3") (pin "1") (pinfunction "1_1") (pintype "passive"))
      (node (ref "P3") (pin "4") (pinfunction "4_4") (pintype "passive"))
      (node (ref "P4") (pin "15") (pinfunction "GND_15") (pintype "passive"))
      (node (ref "P4") (pin "20") (pinfunction "GND_20") (pintype "passive"))
      (node (ref "P4") (pin "28") (pinfunction "GND_28") (pintype "passive"))
      (node (ref "P4") (pin "29") (pinfunction "GND_29") (pintype "passive"))
      (node (ref "P4") (pin "46") (pinfunction "GND_46") (pintype "passive"))
      (node (ref "P4") (pin "47") (pinfunction "GND_47") (pintype "passive"))
      (node (ref "P4") (pin "57") (pinfunction "GND_57") (pintype "passive"))
      (node (ref "P4") (pin "64") (pinfunction "GND_64") (pintype "passive"))
      (node (ref "P4") (pin "71") (pinfunction "GND_71") (pintype "passive"))
      (node (ref "P4") (pin "76") (pinfunction "GND_76") (pintype "passive"))
      (node (ref "P5") (pin "3") (pinfunction "3_3") (pintype "passive"))
      (node (ref "P6") (pin "2") (pinfunction "2_2") (pintype "passive"))
      (node (ref "P7") (pin "1") (pinfunction "1_1") (pintype "passive"))
      (node (ref "P8") (pin "1") (pinfunction "1_1") (pintype "passive"))
      (node (ref "P9") (pin "5") (pinfunction "5_5") (pintype "passive"))
      (node (ref "P9") (pin "6") (pinfunction "6_6") (pintype "passive"))
      (node (ref "Q1") (pin "2") (pinfunction "E_2") (pintype "passive"))
      (node (ref "R10") (pin "2") (pinfunction "2_2") (pintype "passive"))
      (node (ref "R12") (pin "1") (pinfunction "1_1") (pintype "passive"))
      (node (ref "R4") (pin "1") (pinfunction "1_1") (pintype "passive"))
      (node (ref "R5") (pin "1") (pinfunction "1_1") (pintype "passive"))
      (node (ref "R8") (pin "2") (pinfunction "2_2") (pintype "passive"))
      (node (ref "RESET1") (pin "2") (pinfunction "NO_2") (pintype "passive"))
      (node (ref "TPS1") (pin "1") (pinfunction "GND_1") (pintype "passive"))
      (node (ref "TPS2") (pin "1") (pinfunction "GND_1") (pintype "passive"))
      (node (ref "TPS2") (pin "2") (pinfunction "EN_2") (pintype "passive"))
    )
    (net (code "145") (name "MCU_5V") (class "Default")
      (node (ref "C4") (pin "2") (pinfunction "2_2") (pintype "passive"))
      (node (ref "MCU1") (pin "1") (pinfunction "A_1") (pintype "passive"))
      (node (ref "P2") (pin "78") (pinfunction "5V_SYS_78") (pintype "passive"))
      (node (ref "P2") (pin "80") (pinfunction "5V_SYS_80") (pintype "passive"))
      (node (ref "R1") (pin "1") (pinfunction "1_1") (pintype "passive"))
      (node (ref "TPS2") (pin "5") (pinfunction "OUT_5") (pintype "passive"))
      (node (ref "TPS2") (pin "6") (pinfunction "OUT_6") (pintype "passive"))
      (node (ref "TPS2") (pin "7") (pinfunction "FB_7") (pintype "passive"))
    )
    (net (code "146") (name "Net-(*1-B)") (class "Default")
      (node (ref "*1") (pin "1") (pinfunction "B_1") (pintype "passive"))
      (node (ref "R11") (pin "2") (pinfunction "2_2") (pintype "passive"))
      (node (ref "R12") (pin "2") (pinfunction "2_2") (pintype "passive"))
    )
    (net (code "147") (name "Net-(1-K)") (class "Default")
      (node (ref "1") (pin "2") (pinfunction "K_2") (pintype "passive"))
      (node (ref "R4") (pin "2") (pinfunction "2_2") (pintype "passive"))
    )
    (net (code "148") (name "Net-(D1-K)") (class "Default")
      (node (ref "D1") (pin "2") (pinfunction "K_2") (pintype "passive"))
      (node (ref "R8") (pin "1") (pinfunction "1_1") (pintype "passive"))
    )
    (net (code "149") (name "Net-(D2-K)") (class "Default")
      (node (ref "D2") (pin "2") (pinfunction "K_2") (pintype "passive"))
      (node (ref "R10") (pin "1") (pinfunction "1_1") (pintype "passive"))
    )
    (net (code "150") (name "Net-(MCU1-K)") (class "Default")
      (node (ref "MCU1") (pin "2") (pinfunction "K_2") (pintype "passive"))
      (node (ref "R5") (pin "2") (pinfunction "2_2") (pintype "passive"))
    )
    (net (code "151") (name "Net-(PROGRAM1-NO)") (class "Default")
      (node (ref "PROGRAM1") (pin "2") (pinfunction "NO_2") (pintype "passive"))
      (node (ref "R11") (pin "1") (pinfunction "1_1") (pintype "passive"))
      (node (ref "R13") (pin "2") (pinfunction "2_2") (pintype "passive"))
    )
    (net (code "152") (name "Net-(Q1-B)") (class "Default")
      (node (ref "C6") (pin "2") (pinfunction "2_2") (pintype "passive"))
      (node (ref "Q1") (pin "1") (pinfunction "B_1") (pintype "passive"))
      (node (ref "R9") (pin "2") (pinfunction "2_2") (pintype "passive"))
    )
    (net (code "153") (name "Net-(RESET1-COMMON)") (class "Default")
      (node (ref "C5") (pin "1") (pinfunction "1_1") (pintype "passive"))
      (node (ref "R6") (pin "2") (pinfunction "2_2") (pintype "passive"))
      (node (ref "RESET1") (pin "1") (pinfunction "COMMON_1") (pintype "passive"))
    )
    (net (code "154") (name "Net-(SW1-Common)") (class "Default")
      (node (ref "P10") (pin "1") (pinfunction "1_1") (pintype "passive"))
      (node (ref "SW1") (pin "2") (pinfunction "Common_2") (pintype "passive"))
      (node (ref "SW1") (pin "3") (pinfunction "Power_In_3") (pintype "passive"))
    )
    (net (code "155") (name "SERVO_6V") (class "Default")
      (node (ref "P9") (pin "3") (pinfunction "3_3") (pintype "passive"))
      (node (ref "P9") (pin "4") (pinfunction "4_4") (pintype "passive"))
    )
    (net (code "156") (name "unconnected-(P1-Pad12)") (class "Default")
      (node (ref "P1") (pin "12") (pinfunction "12_12") (pintype "passive"))
    )
    (net (code "157") (name "unconnected-(P3-Pad17)") (class "Default")
      (node (ref "P3") (pin "17") (pinfunction "17_17") (pintype "passive+no_connect"))
    )
    (net (code "158") (name "unconnected-(P3-Pad18)") (class "Default")
      (node (ref "P3") (pin "18") (pinfunction "18_18") (pintype "passive+no_connect"))
    )
    (net (code "159") (name "unconnected-(P3-Pad19)") (class "Default")
      (node (ref "P3") (pin "19") (pinfunction "19_19") (pintype "passive+no_connect"))
    )
    (net (code "160") (name "unconnected-(P3-Pad20)") (class "Default")
      (node (ref "P3") (pin "20") (pinfunction "20_20") (pintype "passive+no_connect"))
    )
    (net (code "161") (name "unconnected-(P11-Pad5)") (class "Default")
      (node (ref "P11") (pin "5") (pinfunction "5_5") (pintype "passive"))
    )
    (net (code "162") (name "unconnected-(P11-Pad6)") (class "Default")
      (node (ref "P11") (pin "6") (pinfunction "6_6") (pintype "passive"))
    )
    (net (code "163") (name "unconnected-(TPS1-RESET-Pad8)") (class "Default")
      (node (ref "TPS1") (pin "8") (pinfunction "RESET_8") (pintype "passive+no_connect"))
    )
    (net (code "164") (name "unconnected-(TPS2-RESET-Pad8)") (class "Default")
      (node (ref "TPS2") (pin "8") (pinfunction "RESET_8") (pintype "passive+no_connect"))
    )
  )
)
